# Emon3PVoltageV1_3.net
KiCad netlist of a schematic drawn in EAGLE
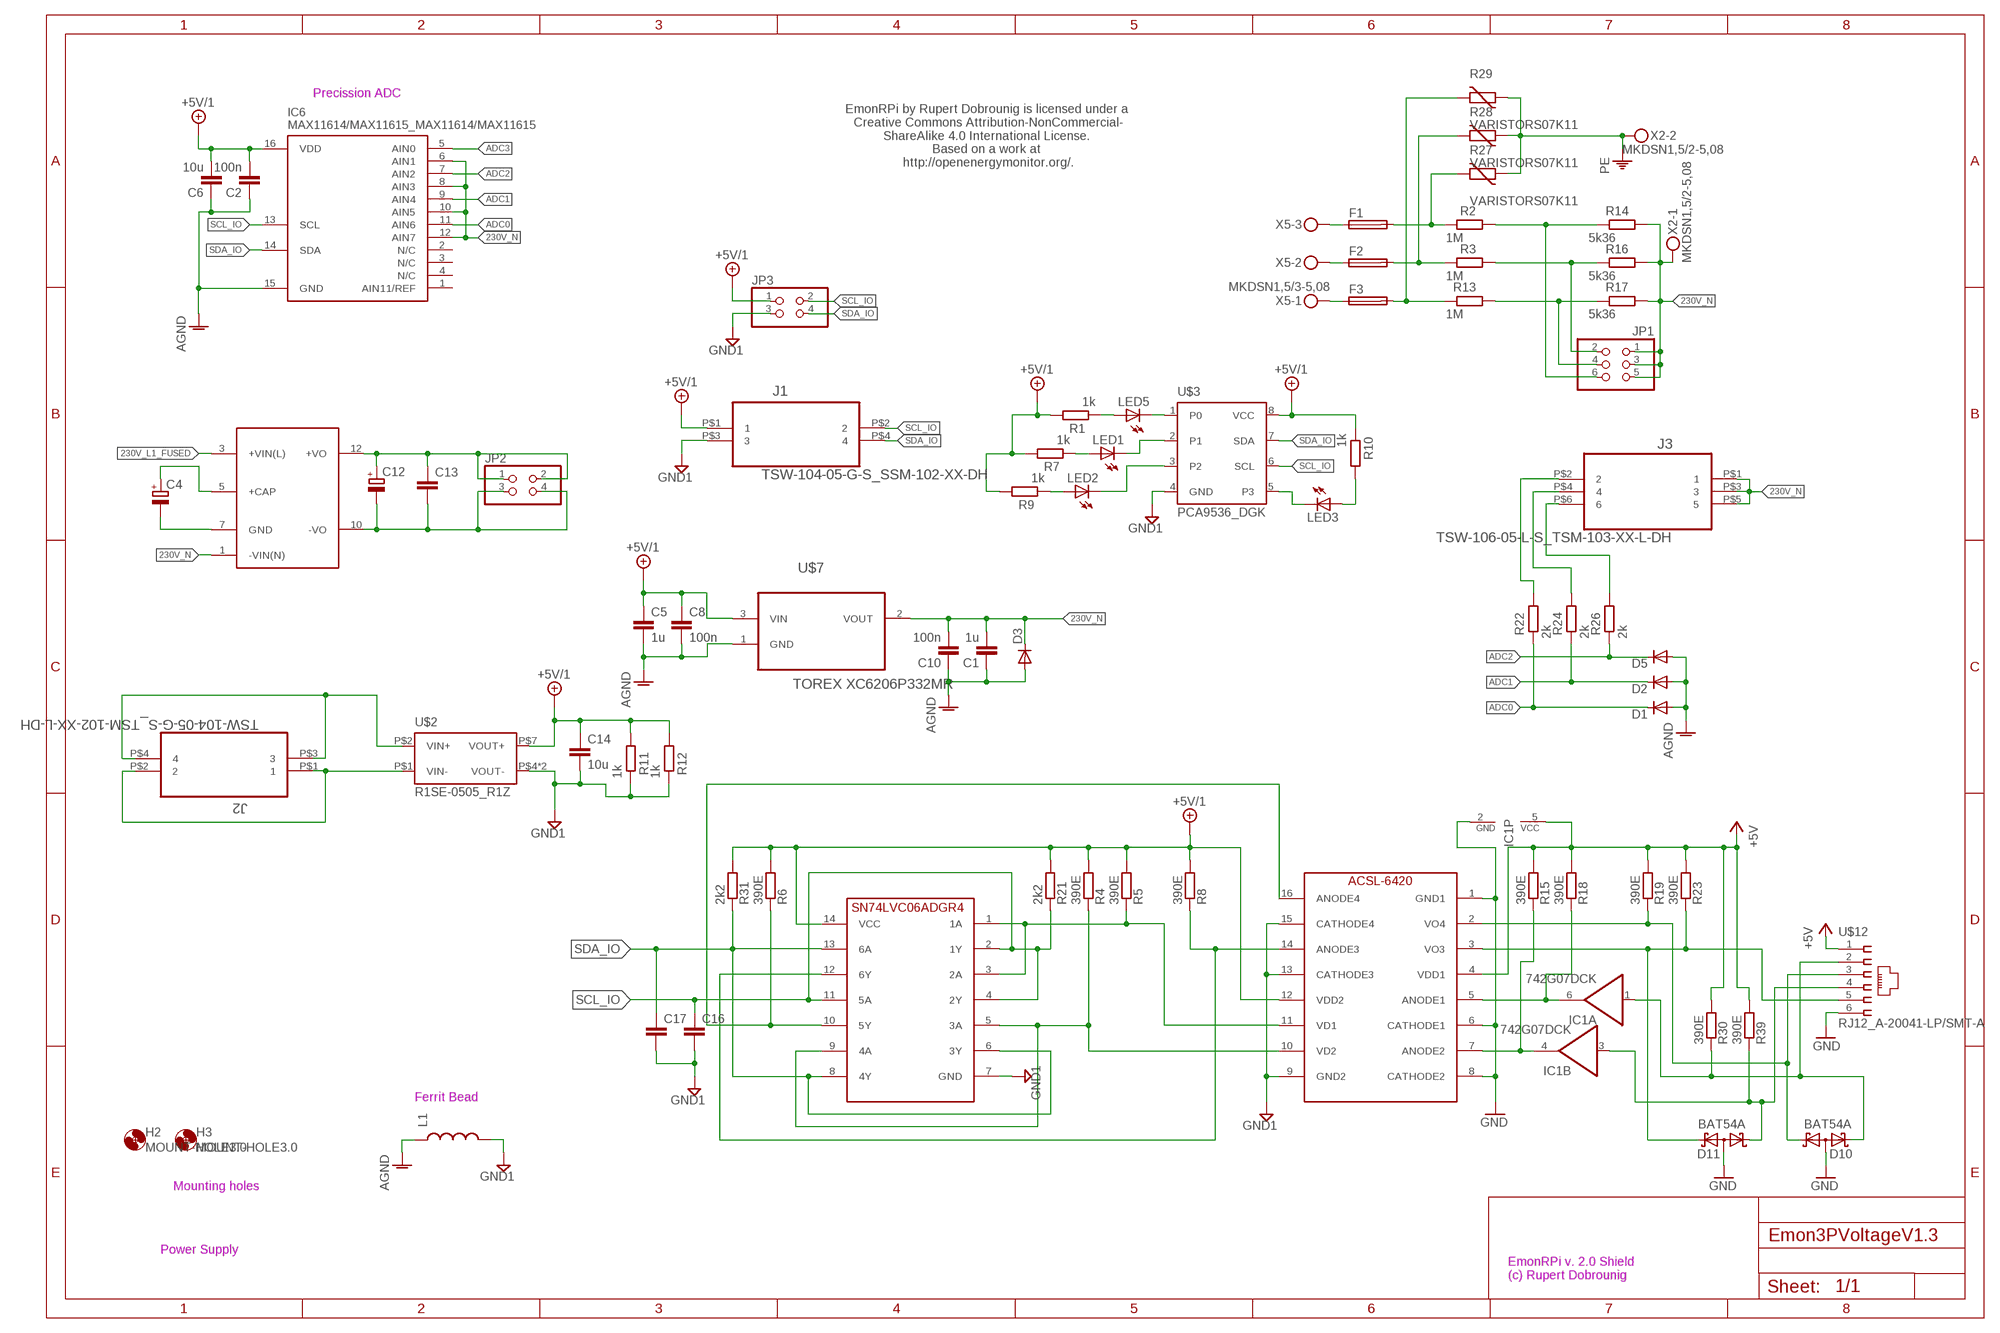
[diagram p0: schematic, sheet 1]

(export (version "E")
  (design (tool "Eeschema 10.0.6"))
  (components
    (comp (ref "C1")
      (value "1u")
      (footprint "eagle-import:C0805")
      (libsource (lib "eagle-import") (part "C-EUC0805"))
    )
    (comp (ref "C2")
      (value "100n")
      (footprint "eagle-import:C0805")
      (libsource (lib "eagle-import") (part "C-EUC0805"))
    )
    (comp (ref "C4")
      (value "CPOL-EUE5-13")
      (footprint "eagle-import:E5-13")
      (libsource (lib "eagle-import") (part "CPOL-EUE5-13"))
    )
    (comp (ref "C5")
      (value "1u")
      (footprint "eagle-import:C0805")
      (libsource (lib "eagle-import") (part "C-EUC0805"))
    )
    (comp (ref "C6")
      (value "10u")
      (footprint "eagle-import:C0805")
      (libsource (lib "eagle-import") (part "C-EUC0805"))
    )
    (comp (ref "C8")
      (value "100n")
      (footprint "eagle-import:C0805")
      (libsource (lib "eagle-import") (part "C-EUC0805"))
    )
    (comp (ref "C10")
      (value "100n")
      (footprint "eagle-import:C0805")
      (libsource (lib "eagle-import") (part "C-EUC0805"))
    )
    (comp (ref "C12")
      (value "CPOL-EUE5-10.5")
      (footprint "eagle-import:E5-10,5")
      (libsource (lib "eagle-import") (part "CPOL-EUE5-10.5"))
    )
    (comp (ref "C13")
      (value "C-EUC0805")
      (footprint "eagle-import:C0805")
      (libsource (lib "eagle-import") (part "C-EUC0805"))
    )
    (comp (ref "C14")
      (value "10u")
      (footprint "eagle-import:C0805")
      (libsource (lib "eagle-import") (part "C-EUC0805"))
    )
    (comp (ref "C16")
      (value "C-EUC0805")
      (footprint "eagle-import:C0805")
      (libsource (lib "eagle-import") (part "C-EUC0805"))
    )
    (comp (ref "C17")
      (value "C-EUC0805")
      (footprint "eagle-import:C0805")
      (libsource (lib "eagle-import") (part "C-EUC0805"))
    )
    (comp (ref "D1")
      (value "DIODE-SOD523")
      (footprint "eagle-import:SOD523")
      (libsource (lib "eagle-import") (part "DIODE-SOD523"))
    )
    (comp (ref "D2")
      (value "DIODE-SOD523")
      (footprint "eagle-import:SOD523")
      (libsource (lib "eagle-import") (part "DIODE-SOD523"))
    )
    (comp (ref "D3")
      (value "DIODE-SOD523")
      (footprint "eagle-import:SOD523")
      (libsource (lib "eagle-import") (part "DIODE-SOD523"))
    )
    (comp (ref "D5")
      (value "DIODE-SOD523")
      (footprint "eagle-import:SOD523")
      (libsource (lib "eagle-import") (part "DIODE-SOD523"))
    )
    (comp (ref "D10")
      (value "BAT54A")
      (footprint "eagle-import:SOT23")
      (libsource (lib "eagle-import") (part "BAT54A"))
    )
    (comp (ref "D11")
      (value "BAT54A")
      (footprint "eagle-import:SOT23")
      (libsource (lib "eagle-import") (part "BAT54A"))
    )
    (comp (ref "F1")
      (value "TE5")
      (footprint "eagle-import:TE5")
      (libsource (lib "eagle-import") (part "TE5"))
    )
    (comp (ref "F2")
      (value "TE5")
      (footprint "eagle-import:TE5")
      (libsource (lib "eagle-import") (part "TE5"))
    )
    (comp (ref "F3")
      (value "TE5")
      (footprint "eagle-import:TE5")
      (libsource (lib "eagle-import") (part "TE5"))
    )
    (comp (ref "H2")
      (value "MOUNT-HOLE3.0")
      (footprint "eagle-import:3,0")
      (libsource (lib "eagle-import") (part "MOUNT-HOLE3.0"))
    )
    (comp (ref "H3")
      (value "MOUNT-HOLE3.0")
      (footprint "eagle-import:3,0")
      (libsource (lib "eagle-import") (part "MOUNT-HOLE3.0"))
    )
    (comp (ref "IC1")
      (value "742G07DCK")
      (footprint "eagle-import:SC70-6")
      (libsource (lib "eagle-import") (part "742G07DCK"))
    )
    (comp (ref "IC6")
      (value "MAX11614/MAX11615_MAX11614/MAX11615")
      (footprint "eagle-import:QSOP16_2")
      (libsource (lib "eagle-import") (part "MAX11614/MAX11615_MAX11614/MAX11615"))
    )
    (comp (ref "J1")
      (value "TSW-104-05-G-S_SSM-102-XX-DH")
      (footprint "eagle-import:SAMTEC_SSM-102-XX-DH")
      (libsource (lib "eagle-import") (part "TSW-104-05-G-S_SSM-102-XX-DH"))
    )
    (comp (ref "J2")
      (value "TSW-104-05-G-S_TSM-102-XX-L-DH")
      (footprint "eagle-import:SAMTEC_TSM-102-XX-L-DH")
      (libsource (lib "eagle-import") (part "TSW-104-05-G-S_TSM-102-XX-L-DH"))
    )
    (comp (ref "J3")
      (value "TSW-106-05-L-S_TSM-103-XX-L-DH")
      (footprint "eagle-import:SAMTEC_TSM-103-XX-L-DH")
      (libsource (lib "eagle-import") (part "TSW-106-05-L-S_TSM-103-XX-L-DH"))
    )
    (comp (ref "JP1")
      (value "PINHD-2X3")
      (footprint "eagle-import:2X03")
      (libsource (lib "eagle-import") (part "PINHD-2X3"))
    )
    (comp (ref "JP2")
      (value "PINHD-2X2")
      (footprint "eagle-import:2X02")
      (libsource (lib "eagle-import") (part "PINHD-2X2"))
    )
    (comp (ref "JP3")
      (value "PINHD-2X2")
      (footprint "eagle-import:2X02")
      (libsource (lib "eagle-import") (part "PINHD-2X2"))
    )
    (comp (ref "L1")
      (value "INDUCTOR0805")
      (footprint "eagle-import:0805")
      (libsource (lib "eagle-import") (part "INDUCTOR0805"))
    )
    (comp (ref "LED1")
      (value "LEDCHIPLED_1206")
      (footprint "eagle-import:CHIPLED_1206")
      (libsource (lib "eagle-import") (part "LEDCHIPLED_1206"))
    )
    (comp (ref "LED2")
      (value "LEDCHIPLED_1206")
      (footprint "eagle-import:CHIPLED_1206")
      (libsource (lib "eagle-import") (part "LEDCHIPLED_1206"))
    )
    (comp (ref "LED3")
      (value "LEDCHIPLED_1206")
      (footprint "eagle-import:CHIPLED_1206")
      (libsource (lib "eagle-import") (part "LEDCHIPLED_1206"))
    )
    (comp (ref "LED5")
      (value "LEDCHIPLED_1206")
      (footprint "eagle-import:CHIPLED_1206")
      (libsource (lib "eagle-import") (part "LEDCHIPLED_1206"))
    )
    (comp (ref "R1")
      (value "1k")
      (footprint "eagle-import:R1206")
      (libsource (lib "eagle-import") (part "R-EU_R1206"))
    )
    (comp (ref "R2")
      (value "1M")
      (footprint "eagle-import:0207_12")
      (libsource (lib "eagle-import") (part "R-EU_0207/12"))
    )
    (comp (ref "R3")
      (value "1M")
      (footprint "eagle-import:0207_12")
      (libsource (lib "eagle-import") (part "R-EU_0207/12"))
    )
    (comp (ref "R4")
      (value "390E")
      (footprint "eagle-import:R1206")
      (libsource (lib "eagle-import") (part "R-EU_R1206"))
    )
    (comp (ref "R5")
      (value "390E")
      (footprint "eagle-import:R1206")
      (libsource (lib "eagle-import") (part "R-EU_R1206"))
    )
    (comp (ref "R6")
      (value "390E")
      (footprint "eagle-import:R1206")
      (libsource (lib "eagle-import") (part "R-EU_R1206"))
    )
    (comp (ref "R7")
      (value "1k")
      (footprint "eagle-import:R1206")
      (libsource (lib "eagle-import") (part "R-EU_R1206"))
    )
    (comp (ref "R8")
      (value "390E")
      (footprint "eagle-import:R1206")
      (libsource (lib "eagle-import") (part "R-EU_R1206"))
    )
    (comp (ref "R9")
      (value "1k")
      (footprint "eagle-import:R1206")
      (libsource (lib "eagle-import") (part "R-EU_R1206"))
    )
    (comp (ref "R10")
      (value "1k")
      (footprint "eagle-import:R1206")
      (libsource (lib "eagle-import") (part "R-EU_R1206"))
    )
    (comp (ref "R11")
      (value "1k")
      (footprint "eagle-import:R1206")
      (libsource (lib "eagle-import") (part "R-EU_R1206"))
    )
    (comp (ref "R12")
      (value "1k")
      (footprint "eagle-import:R1206")
      (libsource (lib "eagle-import") (part "R-EU_R1206"))
    )
    (comp (ref "R13")
      (value "1M")
      (footprint "eagle-import:0207_12")
      (libsource (lib "eagle-import") (part "R-EU_0207/12"))
    )
    (comp (ref "R14")
      (value "5k36")
      (footprint "eagle-import:R1206")
      (libsource (lib "eagle-import") (part "R-EU_R1206"))
    )
    (comp (ref "R15")
      (value "390E")
      (footprint "eagle-import:R1206")
      (libsource (lib "eagle-import") (part "R-EU_R1206"))
    )
    (comp (ref "R16")
      (value "5k36")
      (footprint "eagle-import:R1206")
      (libsource (lib "eagle-import") (part "R-EU_R1206"))
    )
    (comp (ref "R17")
      (value "5k36")
      (footprint "eagle-import:R1206")
      (libsource (lib "eagle-import") (part "R-EU_R1206"))
    )
    (comp (ref "R18")
      (value "390E")
      (footprint "eagle-import:R1206")
      (libsource (lib "eagle-import") (part "R-EU_R1206"))
    )
    (comp (ref "R19")
      (value "390E")
      (footprint "eagle-import:R1206")
      (libsource (lib "eagle-import") (part "R-EU_R1206"))
    )
    (comp (ref "R21")
      (value "2k2")
      (footprint "eagle-import:R1206")
      (libsource (lib "eagle-import") (part "R-EU_R1206"))
    )
    (comp (ref "R22")
      (value "2k")
      (footprint "eagle-import:R1206")
      (libsource (lib "eagle-import") (part "R-EU_R1206"))
    )
    (comp (ref "R23")
      (value "390E")
      (footprint "eagle-import:R1206")
      (libsource (lib "eagle-import") (part "R-EU_R1206"))
    )
    (comp (ref "R24")
      (value "2k")
      (footprint "eagle-import:R1206")
      (libsource (lib "eagle-import") (part "R-EU_R1206"))
    )
    (comp (ref "R26")
      (value "2k")
      (footprint "eagle-import:R1206")
      (libsource (lib "eagle-import") (part "R-EU_R1206"))
    )
    (comp (ref "R27")
      (value "VARISTORS07K11")
      (footprint "eagle-import:S07K11")
      (libsource (lib "eagle-import") (part "VARISTORS07K11"))
    )
    (comp (ref "R28")
      (value "VARISTORS07K11")
      (footprint "eagle-import:S07K11")
      (libsource (lib "eagle-import") (part "VARISTORS07K11"))
    )
    (comp (ref "R29")
      (value "VARISTORS07K11")
      (footprint "eagle-import:S07K11")
      (libsource (lib "eagle-import") (part "VARISTORS07K11"))
    )
    (comp (ref "R30")
      (value "390E")
      (footprint "eagle-import:R1206")
      (libsource (lib "eagle-import") (part "R-EU_R1206"))
    )
    (comp (ref "R31")
      (value "2k2")
      (footprint "eagle-import:R1206")
      (libsource (lib "eagle-import") (part "R-EU_R1206"))
    )
    (comp (ref "R39")
      (value "390E")
      (footprint "eagle-import:R1206")
      (libsource (lib "eagle-import") (part "R-EU_R1206"))
    )
    (comp (ref "U$1")
      (value "LS03-15BXXSR2")
      (footprint "eagle-import:LS03")
      (libsource (lib "eagle-import") (part "LS03-15BXXSR2"))
    )
    (comp (ref "U$2")
      (value "R1SE-0505_R1Z")
      (footprint "eagle-import:R1Z")
      (libsource (lib "eagle-import") (part "R1SE-0505_R1Z"))
    )
    (comp (ref "U$3")
      (value "PCA9536_DGK")
      (footprint "eagle-import:DGK_S-PDSO-G8")
      (libsource (lib "eagle-import") (part "PCA9536_DGK"))
    )
    (comp (ref "U$7")
      (value "TOREX XC6206P332MR")
      (footprint "eagle-import:SOT95P237X112-3N")
      (fields (field (name "MPN") "MCP1700T-3302E/TT"))
      (libsource (lib "eagle-import") (part "MCP1700T-3302E/TT"))
    )
    (comp (ref "U$10")
      (value "ACSL-6420")
      (footprint "eagle-import:SO16")
      (libsource (lib "eagle-import") (part "ACSL-6420"))
    )
    (comp (ref "U$11")
      (value "SN74LVC06ADRG4")
      (footprint "eagle-import:SO-14")
      (libsource (lib "eagle-import") (part "SN74LVC06ADRG4"))
    )
    (comp (ref "U$12")
      (value "RJ12_A-20041-LP/SMT-A")
      (footprint "eagle-import:A-2004-1-LP-SMT-B")
      (libsource (lib "eagle-import") (part "RJ12_A-20041-LP/SMT-A"))
    )
    (comp (ref "X2")
      (value "MKDSN1,5/2-5,08")
      (footprint "eagle-import:MKDSN1,5_2-5,08")
      (fields (field (name "MPN") "MKDSN 1,5/2-5.08"))
      (libsource (lib "eagle-import") (part "MKDSN1,5/2-5,08"))
    )
    (comp (ref "X5")
      (value "MKDSN1,5/3-5,08")
      (footprint "eagle-import:MKDSN1,5_3-5,08")
      (fields (field (name "MPN") "SMKDSN1,5/3-5,08"))
      (libsource (lib "eagle-import") (part "MKDSN1,5/3-5,08"))
    )
  )
  (nets
    (net (code "1") (name "+5V") (class "Default")
      (node (ref "IC1") (pin "5") (pinfunction "VCC_5") (pintype "power_in"))
      (node (ref "R15") (pin "2") (pinfunction "2_2") (pintype "passive"))
      (node (ref "R18") (pin "2") (pinfunction "2_2") (pintype "passive"))
      (node (ref "R19") (pin "2") (pinfunction "2_2") (pintype "passive"))
      (node (ref "R23") (pin "2") (pinfunction "2_2") (pintype "passive"))
      (node (ref "R30") (pin "2") (pinfunction "2_2") (pintype "passive"))
      (node (ref "R39") (pin "2") (pinfunction "2_2") (pintype "passive"))
      (node (ref "U$10") (pin "4") (pinfunction "VDD1_4") (pintype "bidirectional"))
      (node (ref "U$12") (pin "1") (pinfunction "1_1") (pintype "passive"))
    )
    (net (code "2") (name "+5V{slash}1") (class "Default")
      (node (ref "C14") (pin "1") (pinfunction "1_1") (pintype "passive"))
      (node (ref "C2") (pin "2") (pinfunction "2_2") (pintype "passive"))
      (node (ref "C5") (pin "1") (pinfunction "1_1") (pintype "passive"))
      (node (ref "C6") (pin "2") (pinfunction "2_2") (pintype "passive"))
      (node (ref "C8") (pin "1") (pinfunction "1_1") (pintype "passive"))
      (node (ref "IC6") (pin "16") (pinfunction "VDD_16") (pintype "power_in"))
      (node (ref "J1") (pin "P$1") (pinfunction "1_P$1") (pintype "passive"))
      (node (ref "JP3") (pin "1") (pinfunction "1_1") (pintype "passive"))
      (node (ref "R1") (pin "1") (pinfunction "1_1") (pintype "passive"))
      (node (ref "R10") (pin "2") (pinfunction "2_2") (pintype "passive"))
      (node (ref "R11") (pin "1") (pinfunction "1_1") (pintype "passive"))
      (node (ref "R12") (pin "1") (pinfunction "1_1") (pintype "passive"))
      (node (ref "R21") (pin "2") (pinfunction "2_2") (pintype "passive"))
      (node (ref "R31") (pin "2") (pinfunction "2_2") (pintype "passive"))
      (node (ref "R4") (pin "2") (pinfunction "2_2") (pintype "passive"))
      (node (ref "R5") (pin "2") (pinfunction "2_2") (pintype "passive"))
      (node (ref "R6") (pin "2") (pinfunction "2_2") (pintype "passive"))
      (node (ref "R7") (pin "1") (pinfunction "1_1") (pintype "passive"))
      (node (ref "R8") (pin "2") (pinfunction "2_2") (pintype "passive"))
      (node (ref "R9") (pin "1") (pinfunction "1_1") (pintype "passive"))
      (node (ref "U$10") (pin "12") (pinfunction "VDD2_12") (pintype "bidirectional"))
      (node (ref "U$11") (pin "14") (pinfunction "VCC_14") (pintype "bidirectional"))
      (node (ref "U$2") (pin "P$7") (pinfunction "VOUT+_P$7") (pintype "output"))
      (node (ref "U$3") (pin "8") (pinfunction "VCC_8") (pintype "power_in"))
      (node (ref "U$7") (pin "3") (pinfunction "VIN_3") (pintype "input"))
    )
    (net (code "3") (name "230V_L1_FUSED") (class "Default")
      (node (ref "F1") (pin "2") (pinfunction "2_2") (pintype "passive"))
      (node (ref "R2") (pin "2") (pinfunction "2_2") (pintype "passive"))
      (node (ref "R27") (pin "2") (pinfunction "2_2") (pintype "passive"))
      (node (ref "U$1") (pin "3") (pinfunction "+VIN(L)_3") (pintype "power_in"))
    )
    (net (code "4") (name "230V_N") (class "Default")
      (node (ref "C1") (pin "2") (pinfunction "2_2") (pintype "passive"))
      (node (ref "C10") (pin "2") (pinfunction "2_2") (pintype "passive"))
      (node (ref "D3") (pin "C") (pinfunction "C_C") (pintype "passive"))
      (node (ref "IC6") (pin "10") (pinfunction "AIN5_10") (pintype "input"))
      (node (ref "IC6") (pin "12") (pinfunction "AIN7_12") (pintype "input"))
      (node (ref "IC6") (pin "6") (pinfunction "AIN1_6") (pintype "input"))
      (node (ref "IC6") (pin "8") (pinfunction "AIN3_8") (pintype "input"))
      (node (ref "J3") (pin "P$1") (pinfunction "1_P$1") (pintype "passive"))
      (node (ref "J3") (pin "P$3") (pinfunction "3_P$3") (pintype "passive"))
      (node (ref "J3") (pin "P$5") (pinfunction "5_P$5") (pintype "passive"))
      (node (ref "JP1") (pin "1") (pinfunction "1_1") (pintype "passive"))
      (node (ref "JP1") (pin "3") (pinfunction "3_3") (pintype "passive"))
      (node (ref "JP1") (pin "5") (pinfunction "5_5") (pintype "passive"))
      (node (ref "R14") (pin "1") (pinfunction "1_1") (pintype "passive"))
      (node (ref "R16") (pin "1") (pinfunction "1_1") (pintype "passive"))
      (node (ref "R17") (pin "1") (pinfunction "1_1") (pintype "passive"))
      (node (ref "U$1") (pin "1") (pinfunction "-VIN(N)_1") (pintype "power_in"))
      (node (ref "U$7") (pin "2") (pinfunction "VOUT_2") (pintype "output"))
      (node (ref "X2") (pin "1") (pinfunction "KL_1") (pintype "passive"))
    )
    (net (code "5") (name "ADC0") (class "Default")
      (node (ref "D1") (pin "C") (pinfunction "C_C") (pintype "passive"))
      (node (ref "IC6") (pin "11") (pinfunction "AIN6_11") (pintype "input"))
      (node (ref "R22") (pin "2") (pinfunction "2_2") (pintype "passive"))
    )
    (net (code "6") (name "ADC1") (class "Default")
      (node (ref "D2") (pin "C") (pinfunction "C_C") (pintype "passive"))
      (node (ref "IC6") (pin "9") (pinfunction "AIN4_9") (pintype "input"))
      (node (ref "R24") (pin "2") (pinfunction "2_2") (pintype "passive"))
    )
    (net (code "7") (name "ADC2") (class "Default")
      (node (ref "D5") (pin "C") (pinfunction "C_C") (pintype "passive"))
      (node (ref "IC6") (pin "7") (pinfunction "AIN2_7") (pintype "input"))
      (node (ref "R26") (pin "2") (pinfunction "2_2") (pintype "passive"))
    )
    (net (code "8") (name "ADC3") (class "Default")
      (node (ref "IC6") (pin "5") (pinfunction "AIN0_5") (pintype "input"))
    )
    (net (code "9") (name "AGND") (class "Default")
      (node (ref "C1") (pin "1") (pinfunction "1_1") (pintype "passive"))
      (node (ref "C10") (pin "1") (pinfunction "1_1") (pintype "passive"))
      (node (ref "C2") (pin "1") (pinfunction "1_1") (pintype "passive"))
      (node (ref "C5") (pin "2") (pinfunction "2_2") (pintype "passive"))
      (node (ref "C6") (pin "1") (pinfunction "1_1") (pintype "passive"))
      (node (ref "C8") (pin "2") (pinfunction "2_2") (pintype "passive"))
      (node (ref "D1") (pin "A") (pinfunction "A_A") (pintype "passive"))
      (node (ref "D2") (pin "A") (pinfunction "A_A") (pintype "passive"))
      (node (ref "D3") (pin "A") (pinfunction "A_A") (pintype "passive"))
      (node (ref "D5") (pin "A") (pinfunction "A_A") (pintype "passive"))
      (node (ref "IC6") (pin "15") (pinfunction "GND_15") (pintype "power_in"))
      (node (ref "L1") (pin "1") (pinfunction "1_1") (pintype "passive"))
      (node (ref "U$7") (pin "1") (pinfunction "GND_1") (pintype "passive"))
    )
    (net (code "10") (name "GND") (class "Default")
      (node (ref "D10") (pin "3") (pinfunction "AA_3") (pintype "passive"))
      (node (ref "D11") (pin "3") (pinfunction "AA_3") (pintype "passive"))
      (node (ref "IC1") (pin "2") (pinfunction "GND_2") (pintype "power_in"))
      (node (ref "U$10") (pin "1") (pinfunction "GND1_1") (pintype "bidirectional"))
      (node (ref "U$10") (pin "6") (pinfunction "CATHODE1_6") (pintype "bidirectional"))
      (node (ref "U$10") (pin "8") (pinfunction "CATHODE2_8") (pintype "bidirectional"))
      (node (ref "U$12") (pin "6") (pinfunction "6_6") (pintype "passive"))
    )
    (net (code "11") (name "GND1") (class "Default")
      (node (ref "C14") (pin "2") (pinfunction "2_2") (pintype "passive"))
      (node (ref "C16") (pin "2") (pinfunction "2_2") (pintype "passive"))
      (node (ref "C17") (pin "2") (pinfunction "2_2") (pintype "passive"))
      (node (ref "J1") (pin "P$3") (pinfunction "3_P$3") (pintype "passive"))
      (node (ref "JP3") (pin "3") (pinfunction "3_3") (pintype "passive"))
      (node (ref "L1") (pin "2") (pinfunction "2_2") (pintype "passive"))
      (node (ref "R11") (pin "2") (pinfunction "2_2") (pintype "passive"))
      (node (ref "R12") (pin "2") (pinfunction "2_2") (pintype "passive"))
      (node (ref "U$10") (pin "13") (pinfunction "CATHODE3_13") (pintype "bidirectional"))
      (node (ref "U$10") (pin "15") (pinfunction "CATHODE4_15") (pintype "bidirectional"))
      (node (ref "U$10") (pin "9") (pinfunction "GND2_9") (pintype "bidirectional"))
      (node (ref "U$11") (pin "7") (pinfunction "GND_7") (pintype "bidirectional"))
      (node (ref "U$2") (pin "P$4") (pinfunction "VOUT-_P$4") (pintype "output"))
      (node (ref "U$2") (pin "P$5") (pinfunction "VOUT-_P$5") (pintype "output"))
      (node (ref "U$3") (pin "4") (pinfunction "GND_4") (pintype "power_in"))
    )
    (net (code "12") (name "Net-(D10-K1)") (class "Default")
      (node (ref "D10") (pin "1") (pinfunction "K1_1") (pintype "passive"))
      (node (ref "R19") (pin "1") (pinfunction "1_1") (pintype "passive"))
      (node (ref "U$10") (pin "2") (pinfunction "VO4_2") (pintype "bidirectional"))
      (node (ref "U$12") (pin "3") (pinfunction "3_3") (pintype "passive"))
    )
    (net (code "13") (name "Net-(D10-K2)") (class "Default")
      (node (ref "D10") (pin "2") (pinfunction "K2_2") (pintype "passive"))
      (node (ref "IC1") (pin "1") (pinfunction "I_1") (pintype "input"))
      (node (ref "R30") (pin "1") (pinfunction "1_1") (pintype "passive"))
      (node (ref "U$12") (pin "2") (pinfunction "2_2") (pintype "passive"))
    )
    (net (code "14") (name "Net-(D11-K1)") (class "Default")
      (node (ref "D11") (pin "1") (pinfunction "K1_1") (pintype "passive"))
      (node (ref "IC1") (pin "3") (pinfunction "I_3") (pintype "input"))
      (node (ref "R39") (pin "1") (pinfunction "1_1") (pintype "passive"))
      (node (ref "U$12") (pin "4") (pinfunction "4_4") (pintype "passive"))
    )
    (net (code "15") (name "Net-(D11-K2)") (class "Default")
      (node (ref "D11") (pin "2") (pinfunction "K2_2") (pintype "passive"))
      (node (ref "R23") (pin "1") (pinfunction "1_1") (pintype "passive"))
      (node (ref "U$10") (pin "3") (pinfunction "VO3_3") (pintype "bidirectional"))
      (node (ref "U$12") (pin "5") (pinfunction "5_5") (pintype "passive"))
    )
    (net (code "16") (name "Net-(F2-Pad2)") (class "Default")
      (node (ref "F2") (pin "2") (pinfunction "2_2") (pintype "passive"))
      (node (ref "R28") (pin "2") (pinfunction "2_2") (pintype "passive"))
      (node (ref "R3") (pin "2") (pinfunction "2_2") (pintype "passive"))
    )
    (net (code "17") (name "Net-(F3-Pad2)") (class "Default")
      (node (ref "F3") (pin "2") (pinfunction "2_2") (pintype "passive"))
      (node (ref "R13") (pin "2") (pinfunction "2_2") (pintype "passive"))
      (node (ref "R29") (pin "2") (pinfunction "2_2") (pintype "passive"))
    )
    (net (code "18") (name "Net-(IC1A-O)") (class "Default")
      (node (ref "IC1") (pin "6") (pinfunction "O_6") (pintype "open_collector"))
      (node (ref "R18") (pin "1") (pinfunction "1_1") (pintype "passive"))
      (node (ref "U$10") (pin "5") (pinfunction "ANODE1_5") (pintype "bidirectional"))
    )
    (net (code "19") (name "Net-(IC1B-O)") (class "Default")
      (node (ref "IC1") (pin "4") (pinfunction "O_4") (pintype "open_collector"))
      (node (ref "R15") (pin "1") (pinfunction "1_1") (pintype "passive"))
      (node (ref "U$10") (pin "7") (pinfunction "ANODE2_7") (pintype "bidirectional"))
    )
    (net (code "20") (name "Net-(J2-1)") (class "Default")
      (node (ref "J2") (pin "P$1") (pinfunction "1_P$1") (pintype "passive"))
      (node (ref "J2") (pin "P$2") (pinfunction "2_P$2") (pintype "passive"))
      (node (ref "U$2") (pin "P$1") (pinfunction "VIN-_P$1") (pintype "input"))
    )
    (net (code "21") (name "Net-(J2-3)") (class "Default")
      (node (ref "J2") (pin "P$3") (pinfunction "3_P$3") (pintype "passive"))
      (node (ref "J2") (pin "P$4") (pinfunction "4_P$4") (pintype "passive"))
      (node (ref "U$2") (pin "P$2") (pinfunction "VIN+_P$2") (pintype "input"))
    )
    (net (code "22") (name "Net-(J3-2)") (class "Default")
      (node (ref "J3") (pin "P$2") (pinfunction "2_P$2") (pintype "passive"))
      (node (ref "R22") (pin "1") (pinfunction "1_1") (pintype "passive"))
    )
    (net (code "23") (name "Net-(J3-4)") (class "Default")
      (node (ref "J3") (pin "P$4") (pinfunction "4_P$4") (pintype "passive"))
      (node (ref "R24") (pin "1") (pinfunction "1_1") (pintype "passive"))
    )
    (net (code "24") (name "Net-(J3-6)") (class "Default")
      (node (ref "J3") (pin "P$6") (pinfunction "6_P$6") (pintype "passive"))
      (node (ref "R26") (pin "1") (pinfunction "1_1") (pintype "passive"))
    )
    (net (code "25") (name "Net-(JP1-Pad2)") (class "Default")
      (node (ref "JP1") (pin "2") (pinfunction "2_2") (pintype "passive"))
      (node (ref "R16") (pin "2") (pinfunction "2_2") (pintype "passive"))
      (node (ref "R3") (pin "1") (pinfunction "1_1") (pintype "passive"))
    )
    (net (code "26") (name "Net-(JP1-Pad4)") (class "Default")
      (node (ref "JP1") (pin "4") (pinfunction "4_4") (pintype "passive"))
      (node (ref "R13") (pin "1") (pinfunction "1_1") (pintype "passive"))
      (node (ref "R17") (pin "2") (pinfunction "2_2") (pintype "passive"))
    )
    (net (code "27") (name "Net-(JP1-Pad6)") (class "Default")
      (node (ref "JP1") (pin "6") (pinfunction "6_6") (pintype "passive"))
      (node (ref "R14") (pin "2") (pinfunction "2_2") (pintype "passive"))
      (node (ref "R2") (pin "1") (pinfunction "1_1") (pintype "passive"))
    )
    (net (code "28") (name "Net-(LED1-PadA)") (class "Default")
      (node (ref "LED1") (pin "A") (pinfunction "A_A") (pintype "passive"))
      (node (ref "R7") (pin "2") (pinfunction "2_2") (pintype "passive"))
    )
    (net (code "29") (name "Net-(LED2-PadA)") (class "Default")
      (node (ref "LED2") (pin "A") (pinfunction "A_A") (pintype "passive"))
      (node (ref "R9") (pin "2") (pinfunction "2_2") (pintype "passive"))
    )
    (net (code "30") (name "Net-(LED3-PadA)") (class "Default")
      (node (ref "LED3") (pin "A") (pinfunction "A_A") (pintype "passive"))
      (node (ref "R10") (pin "1") (pinfunction "1_1") (pintype "passive"))
    )
    (net (code "31") (name "Net-(LED5-PadA)") (class "Default")
      (node (ref "LED5") (pin "A") (pinfunction "A_A") (pintype "passive"))
      (node (ref "R1") (pin "2") (pinfunction "2_2") (pintype "passive"))
    )
    (net (code "32") (name "Net-(U$1-+CAP)") (class "Default")
      (node (ref "C4") (pin "+") (pinfunction "+_+") (pintype "passive"))
      (node (ref "U$1") (pin "5") (pinfunction "+CAP_5") (pintype "passive"))
    )
    (net (code "33") (name "Net-(U$1-+VO)") (class "Default")
      (node (ref "C12") (pin "+") (pinfunction "+_+") (pintype "passive"))
      (node (ref "C13") (pin "1") (pinfunction "1_1") (pintype "passive"))
      (node (ref "JP2") (pin "1") (pinfunction "1_1") (pintype "passive"))
      (node (ref "JP2") (pin "2") (pinfunction "2_2") (pintype "passive"))
      (node (ref "U$1") (pin "12") (pinfunction "+VO_12") (pintype "power_in"))
    )
    (net (code "34") (name "Net-(U$1--VO)") (class "Default")
      (node (ref "C12") (pin "-") (pinfunction "-_-") (pintype "passive"))
      (node (ref "C13") (pin "2") (pinfunction "2_2") (pintype "passive"))
      (node (ref "JP2") (pin "3") (pinfunction "3_3") (pintype "passive"))
      (node (ref "JP2") (pin "4") (pinfunction "4_4") (pintype "passive"))
      (node (ref "U$1") (pin "10") (pinfunction "-VO_10") (pintype "power_in"))
    )
    (net (code "35") (name "Net-(U$1-GND)") (class "Default")
      (node (ref "C4") (pin "-") (pinfunction "-_-") (pintype "passive"))
      (node (ref "U$1") (pin "7") (pinfunction "GND_7") (pintype "passive"))
    )
    (net (code "36") (name "Net-(U$3-P0)") (class "Default")
      (node (ref "LED5") (pin "C") (pinfunction "C_C") (pintype "passive"))
      (node (ref "U$3") (pin "1") (pinfunction "P0_1") (pintype "bidirectional"))
    )
    (net (code "37") (name "Net-(U$3-P1)") (class "Default")
      (node (ref "LED1") (pin "C") (pinfunction "C_C") (pintype "passive"))
      (node (ref "U$3") (pin "2") (pinfunction "P1_2") (pintype "bidirectional"))
    )
    (net (code "38") (name "Net-(U$3-P2)") (class "Default")
      (node (ref "LED2") (pin "C") (pinfunction "C_C") (pintype "passive"))
      (node (ref "U$3") (pin "3") (pinfunction "P2_3") (pintype "bidirectional"))
    )
    (net (code "39") (name "Net-(U$3-P3)") (class "Default")
      (node (ref "LED3") (pin "C") (pinfunction "C_C") (pintype "passive"))
      (node (ref "U$3") (pin "5") (pinfunction "P3_5") (pintype "bidirectional"))
    )
    (net (code "40") (name "Net-(U$10-ANODE3)") (class "Default")
      (node (ref "R8") (pin "1") (pinfunction "1_1") (pintype "passive"))
      (node (ref "U$10") (pin "14") (pinfunction "ANODE3_14") (pintype "bidirectional"))
      (node (ref "U$11") (pin "12") (pinfunction "6Y_12") (pintype "bidirectional"))
    )
    (net (code "41") (name "Net-(U$10-ANODE4)") (class "Default")
      (node (ref "R6") (pin "1") (pinfunction "1_1") (pintype "passive"))
      (node (ref "U$10") (pin "16") (pinfunction "ANODE4_16") (pintype "bidirectional"))
      (node (ref "U$11") (pin "10") (pinfunction "5Y_10") (pintype "bidirectional"))
    )
    (net (code "42") (name "Net-(U$10-VD1)") (class "Default")
      (node (ref "R5") (pin "1") (pinfunction "1_1") (pintype "passive"))
      (node (ref "U$10") (pin "11") (pinfunction "VD1_11") (pintype "bidirectional"))
      (node (ref "U$11") (pin "1") (pinfunction "1A_1") (pintype "bidirectional"))
      (node (ref "U$11") (pin "3") (pinfunction "2A_3") (pintype "bidirectional"))
    )
    (net (code "43") (name "Net-(U$10-VD2)") (class "Default")
      (node (ref "R4") (pin "1") (pinfunction "1_1") (pintype "passive"))
      (node (ref "U$10") (pin "10") (pinfunction "VD2_10") (pintype "bidirectional"))
      (node (ref "U$11") (pin "5") (pinfunction "3A_5") (pintype "bidirectional"))
      (node (ref "U$11") (pin "9") (pinfunction "4A_9") (pintype "bidirectional"))
    )
    (net (code "44") (name "Net-(X5A-KL)") (class "Default")
      (node (ref "F3") (pin "1") (pinfunction "1_1") (pintype "passive"))
      (node (ref "X5") (pin "1") (pinfunction "KL_1") (pintype "passive"))
    )
    (net (code "45") (name "Net-(X5B-KL)") (class "Default")
      (node (ref "F2") (pin "1") (pinfunction "1_1") (pintype "passive"))
      (node (ref "X5") (pin "2") (pinfunction "KL_2") (pintype "passive"))
    )
    (net (code "46") (name "Net-(X5C-KL)") (class "Default")
      (node (ref "F1") (pin "1") (pinfunction "1_1") (pintype "passive"))
      (node (ref "X5") (pin "3") (pinfunction "KL_3") (pintype "passive"))
    )
    (net (code "47") (name "PE") (class "Default")
      (node (ref "R27") (pin "1") (pinfunction "1_1") (pintype "passive"))
      (node (ref "R28") (pin "1") (pinfunction "1_1") (pintype "passive"))
      (node (ref "R29") (pin "1") (pinfunction "1_1") (pintype "passive"))
      (node (ref "X2") (pin "2") (pinfunction "KL_2") (pintype "passive"))
    )
    (net (code "48") (name "SCL_IO") (class "Default")
      (node (ref "C16") (pin "1") (pinfunction "1_1") (pintype "passive"))
      (node (ref "IC6") (pin "13") (pinfunction "SCL_13") (pintype "bidirectional"))
      (node (ref "J1") (pin "P$2") (pinfunction "2_P$2") (pintype "passive"))
      (node (ref "JP3") (pin "2") (pinfunction "2_2") (pintype "passive"))
      (node (ref "R21") (pin "1") (pinfunction "1_1") (pintype "passive"))
      (node (ref "U$11") (pin "11") (pinfunction "5A_11") (pintype "bidirectional"))
      (node (ref "U$11") (pin "2") (pinfunction "1Y_2") (pintype "bidirectional"))
      (node (ref "U$11") (pin "4") (pinfunction "2Y_4") (pintype "bidirectional"))
      (node (ref "U$3") (pin "6") (pinfunction "SCL_6") (pintype "input"))
    )
    (net (code "49") (name "SDA_IO") (class "Default")
      (node (ref "C17") (pin "1") (pinfunction "1_1") (pintype "passive"))
      (node (ref "IC6") (pin "14") (pinfunction "SDA_14") (pintype "bidirectional"))
      (node (ref "J1") (pin "P$4") (pinfunction "4_P$4") (pintype "passive"))
      (node (ref "JP3") (pin "4") (pinfunction "4_4") (pintype "passive"))
      (node (ref "R31") (pin "1") (pinfunction "1_1") (pintype "passive"))
      (node (ref "U$11") (pin "13") (pinfunction "6A_13") (pintype "bidirectional"))
      (node (ref "U$11") (pin "6") (pinfunction "3Y_6") (pintype "bidirectional"))
      (node (ref "U$11") (pin "8") (pinfunction "4Y_8") (pintype "bidirectional"))
      (node (ref "U$3") (pin "7") (pinfunction "SDA_7") (pintype "bidirectional"))
    )
    (net (code "50") (name "unconnected-(IC6-AIN11{slash}REF-Pad1)") (class "Default")
      (node (ref "IC6") (pin "1") (pinfunction "AIN11/REF_1") (pintype "bidirectional"))
    )
    (net (code "51") (name "unconnected-(IC6-N{slash}C-Pad2)") (class "Default")
      (node (ref "IC6") (pin "2") (pinfunction "N/C_2") (pintype "no_connect"))
    )
    (net (code "52") (name "unconnected-(IC6-N{slash}C-Pad3)") (class "Default")
      (node (ref "IC6") (pin "3") (pinfunction "N/C_3") (pintype "no_connect"))
    )
    (net (code "53") (name "unconnected-(IC6-N{slash}C-Pad4)") (class "Default")
      (node (ref "IC6") (pin "4") (pinfunction "N/C_4") (pintype "no_connect"))
    )
  )
)
